# 24_069.net
KiCad netlist of a schematic drawn in Altium Designer
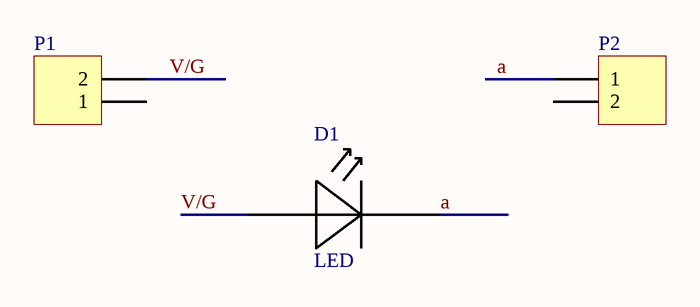
[diagram p0: 24.069.SchDoc]

(export (version "E")
  (design (tool "Eeschema 10.0.6"))
  (components
    (comp (ref "D1") (value "LED") (footprint "LED") (libsource (lib "msp_SchLib") (part "LED")))
    (comp (ref "P1")
      (value "Header 2")
      (footprint "HDR1X2")
      (description "Header, 2-Pin")
      (fields (field (name "PUBLISHER") "Altium Limited"))
      (libsource (lib "Miscellaneous Connectors") (part "Header 2"))
    )
    (comp (ref "P2")
      (value "Header 2")
      (footprint "HDR1X2")
      (description "Header, 2-Pin")
      (fields (field (name "PUBLISHER") "Altium Limited"))
      (libsource (lib "") (part "Header 2_1"))
    )
  )
  (nets
    (net (code "1") (name "/V{slash}G") (class "Default")
      (node (ref "D1") (pin "1") (pinfunction "1_1") (pintype "passive"))
      (node (ref "P1") (pin "2") (pinfunction "2_2") (pintype "passive"))
    )
    (net (code "2") (name "/a") (class "Default")
      (node (ref "D1") (pin "2") (pinfunction "2_2") (pintype "passive"))
      (node (ref "P2") (pin "1") (pinfunction "1_1") (pintype "passive"))
    )
    (net (code "3") (name "unconnected-(P1-Pad1)") (class "Default")
      (node (ref "P1") (pin "1") (pinfunction "1_1") (pintype "passive"))
    )
    (net (code "4") (name "unconnected-(P2-Pad2)") (class "Default")
      (node (ref "P2") (pin "2") (pinfunction "2_2") (pintype "passive"))
    )
  )
)
